# GPS_CAM-M8Q.net
KiCad netlist of a schematic drawn in Altium Designer
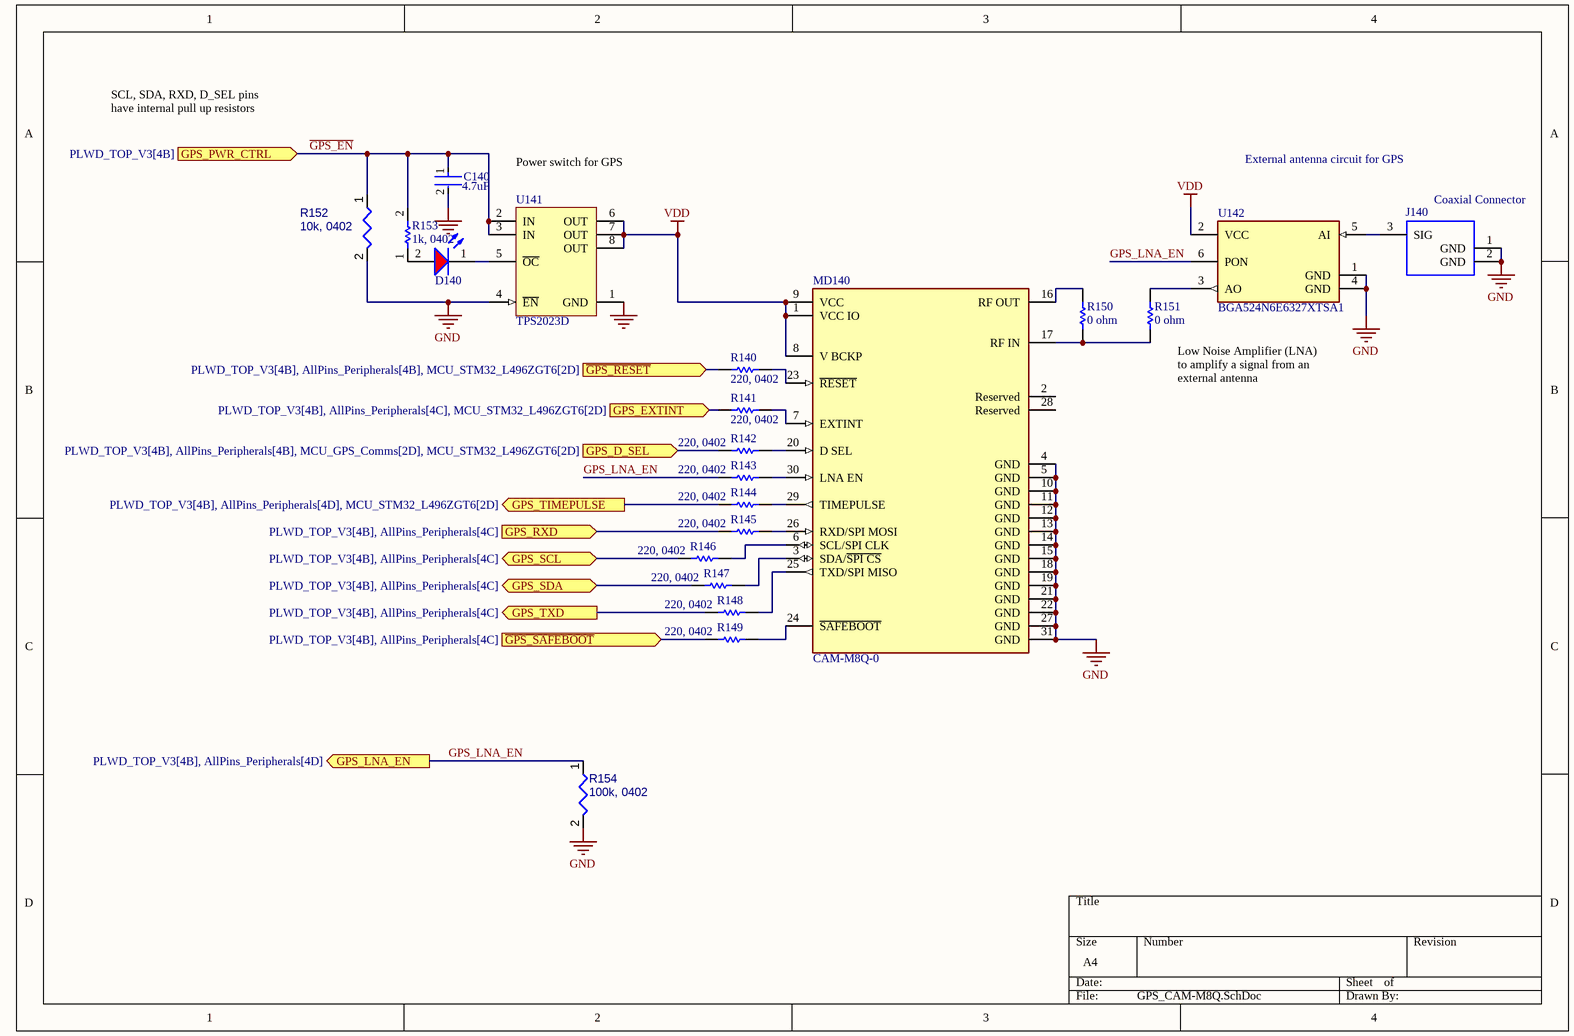
[diagram p0: GPS_CAM-M8Q.SchDoc]

(export (version "E")
  (design (tool "Eeschema 10.0.6"))
  (components
    (comp (ref "C140")
      (value "CL05A475MP5NRNC")
      (footprint "FP-CL282-IPC_C")
      (description "Cap Ceramic 4.7uF 10V X5R ±20% SMD 0402 +85°C Paper T/R")
      (fields (field (name "CAPACITANCE") "4.7uF") (field (name "TOLERANCE") "20%"))
      (libsource (lib "Altium Content Vault") (part "b4654b650e69147ec39a6b967a45e02"))
    )
    (comp (ref "D140")
      (value "150120SS75000")
      (footprint "WL-SMCW_1206_150120xx75000")
      (libsource (lib "Altium Content Vault") (part "LED_Red_2A-1K"))
    )
    (comp (ref "J140")
      (value "Coaxial Connector")
      (footprint "HRS-U.FL-R-SMT_V")
      (fields (field (name "MANUFACTURER") "Hirose Electric"))
      (libsource (lib "Carleton University") (part "HRS-U.FL-R-SMT-3"))
    )
    (comp (ref "MD140")
      (value "CAM-M8Q-0")
      (footprint "FP-CAM-M8Q-0-MFG")
      (description "RF RCVR GNSS/GPS 1.575GHZ MODULE")
      (fields
        (field (name "OCTOPART") "https://octopart.com/cam-m8q-0-u-blox-54356730")
        (field (name "MANUFACTURER") "u-blox")
      )
      (libsource (lib "Altium Content Vault") (part "ce05b97091f8f71e8eae4fd8376787f"))
    )
    (comp (ref "R140")
      (value "220, 0402")
      (footprint "RESC1005X40X25LL10T10")
      (fields (field (name "PART NUMBER") "RK73H1ETTP2200F") (field (name "MANUFACTURER") "KOA Speer"))
      (libsource (lib "Altium Content Vault") (part "RES"))
    )
    (comp (ref "R141")
      (value "220, 0402")
      (footprint "RESC1005X40X25LL10T10")
      (fields (field (name "PART NUMBER") "RK73H1ETTP2200F") (field (name "MANUFACTURER") "KOA Speer"))
      (libsource (lib "Altium Content Vault") (part "RES"))
    )
    (comp (ref "R142")
      (value "220, 0402")
      (footprint "RESC1005X40X25LL10T10")
      (fields (field (name "PART NUMBER") "RK73H1ETTP2200F") (field (name "MANUFACTURER") "KOA Speer"))
      (libsource (lib "Altium Content Vault") (part "RES"))
    )
    (comp (ref "R143")
      (value "220, 0402")
      (footprint "RESC1005X40X25LL10T10")
      (fields (field (name "PART NUMBER") "RK73H1ETTP2200F") (field (name "MANUFACTURER") "KOA Speer"))
      (libsource (lib "Altium Content Vault") (part "RES"))
    )
    (comp (ref "R144")
      (value "220, 0402")
      (footprint "RESC1005X40X25LL10T10")
      (fields (field (name "PART NUMBER") "RK73H1ETTP2200F") (field (name "MANUFACTURER") "KOA Speer"))
      (libsource (lib "Altium Content Vault") (part "RES"))
    )
    (comp (ref "R145")
      (value "220, 0402")
      (footprint "RESC1005X40X25LL10T10")
      (fields (field (name "PART NUMBER") "RK73H1ETTP2200F") (field (name "MANUFACTURER") "KOA Speer"))
      (libsource (lib "Altium Content Vault") (part "RES"))
    )
    (comp (ref "R146")
      (value "220, 0402")
      (footprint "RESC1005X40X25LL10T10")
      (fields (field (name "PART NUMBER") "RK73H1ETTP2200F") (field (name "MANUFACTURER") "KOA Speer"))
      (libsource (lib "Altium Content Vault") (part "RES"))
    )
    (comp (ref "R147")
      (value "220, 0402")
      (footprint "RESC1005X40X25LL10T10")
      (fields (field (name "PART NUMBER") "RK73H1ETTP2200F") (field (name "MANUFACTURER") "KOA Speer"))
      (libsource (lib "Altium Content Vault") (part "RES"))
    )
    (comp (ref "R148")
      (value "220, 0402")
      (footprint "RESC1005X40X25LL10T10")
      (fields (field (name "PART NUMBER") "RK73H1ETTP2200F") (field (name "MANUFACTURER") "KOA Speer"))
      (libsource (lib "Altium Content Vault") (part "RES"))
    )
    (comp (ref "R149")
      (value "220, 0402")
      (footprint "RESC1005X40X25LL10T10")
      (fields (field (name "PART NUMBER") "RK73H1ETTP2200F") (field (name "MANUFACTURER") "KOA Speer"))
      (libsource (lib "Altium Content Vault") (part "RES"))
    )
    (comp (ref "R150")
      (value "0 ohm")
      (footprint "RESC1005X40X25LL05T10")
      (fields (field (name "MANUFACTURER") "Panasonic") (field (name "PART NUMBER") "ERJ-S020R00X"))
      (libsource (lib "Altium Content Vault") (part "RES"))
    )
    (comp (ref "R151")
      (value "0 ohm")
      (footprint "RESC1005X40X25LL05T10")
      (fields (field (name "MANUFACTURER") "Panasonic") (field (name "PART NUMBER") "ERJ-S020R00X"))
      (libsource (lib "Altium Content Vault") (part "RES"))
    )
    (comp (ref "R152")
      (value "10k, 0402")
      (footprint "RESC1005X40X25ML05T05")
      (description "Chip Resistor, 10 KOhm, +/- 1%, 0.1 W, -55 to 155 degC, 0402 (1005 Metric)")
      (fields (field (name "TOLERANCE") "1%") (field (name "POWER") "100mW"))
      (libsource (lib "") (part "RES-2_1"))
    )
    (comp (ref "R153")
      (value "1k, 0402")
      (footprint "RESC1005X40X25ML05T05")
      (description "Chip Resistor, 1 KOhm, +/- 1%, 0.1 W, -55 to 155 degC, 0402 (1005 Metric)")
      (fields (field (name "POWER") "100mW") (field (name "TOLERANCE") "1%"))
      (libsource (lib "Carleton University") (part "RES-2"))
    )
    (comp (ref "R154")
      (value "100k, 0402")
      (footprint "RESC1005X40X25ML05T05")
      (description "Chip Resistor, 100 KOhm, +/- 1%, 0.1 W, -55 to 155 degC, 0402 (1005 Metric)")
      (fields (field (name "POWER") "100mW") (field (name "TOLERANCE") "1%"))
      (libsource (lib "") (part "RES-2_1"))
    )
    (comp (ref "U141")
      (value "TPS2023D")
      (footprint "D0008A_M")
      (fields (field (name "MANUFACTURER") "Texas Instruments"))
      (libsource (lib "Altium Content Vault") (part "TI-TPS2023D8"))
    )
    (comp (ref "U142")
      (value "BGA524N6E6327XTSA1")
      (footprint "FP-PG-TSNP-6-MFG")
      (description "IC AMP GPS 1.55-1.615GHZ TSNP6-2")
      (libsource (lib "Altium Content Vault") (part "f76d869b63f6dd4e076b8b444429d3f"))
    )
  )
  (nets
    (net (code "1") (name "/GPS_D_SEL") (class "Default")
      (node (ref "R142") (pin "2") (pinfunction "2_2") (pintype "passive"))
    )
    (net (code "2") (name "/GPS_EXTINT") (class "Default")
      (node (ref "R141") (pin "2") (pinfunction "2_2") (pintype "passive"))
    )
    (net (code "3") (name "/GPS_LNA_EN") (class "Default")
      (node (ref "R143") (pin "2") (pinfunction "2_2") (pintype "passive"))
      (node (ref "R154") (pin "1") (pinfunction "1_1") (pintype "passive"))
      (node (ref "U142") (pin "6") (pinfunction "PON_6") (pintype "power_in"))
    )
    (net (code "4") (name "/GPS_RXD") (class "Default")
      (node (ref "R145") (pin "2") (pinfunction "2_2") (pintype "passive"))
    )
    (net (code "5") (name "/GPS_SCL") (class "Default")
      (node (ref "R146") (pin "2") (pinfunction "2_2") (pintype "passive"))
    )
    (net (code "6") (name "/GPS_SDA") (class "Default")
      (node (ref "R147") (pin "2") (pinfunction "2_2") (pintype "passive"))
    )
    (net (code "7") (name "/GPS_TIMEPULSE") (class "Default")
      (node (ref "R144") (pin "2") (pinfunction "2_2") (pintype "passive"))
    )
    (net (code "8") (name "/GPS_TXD") (class "Default")
      (node (ref "R148") (pin "2") (pinfunction "2_2") (pintype "passive"))
    )
    (net (code "9") (name "/~{GPS_EN}") (class "Default")
      (node (ref "C140") (pin "1") (pinfunction "1_1") (pintype "passive"))
      (node (ref "R152") (pin "1") (pinfunction "1_1") (pintype "passive"))
      (node (ref "R153") (pin "2") (pinfunction "2_2") (pintype "passive"))
      (node (ref "U141") (pin "2") (pinfunction "IN_2") (pintype "power_in"))
      (node (ref "U141") (pin "3") (pinfunction "IN_3") (pintype "power_in"))
    )
    (net (code "10") (name "/~{GPS_RESET}") (class "Default")
      (node (ref "R140") (pin "2") (pinfunction "2_2") (pintype "passive"))
    )
    (net (code "11") (name "/~{GPS_SAFEBOOT}") (class "Default")
      (node (ref "R149") (pin "2") (pinfunction "2_2") (pintype "passive"))
    )
    (net (code "12") (name "GND") (class "Default")
      (node (ref "C140") (pin "2") (pinfunction "2_2") (pintype "passive"))
      (node (ref "J140") (pin "1") (pinfunction "GND_1") (pintype "power_in"))
      (node (ref "J140") (pin "2") (pinfunction "GND_2") (pintype "power_in"))
      (node (ref "MD140") (pin "10") (pinfunction "GND_10") (pintype "power_in"))
      (node (ref "MD140") (pin "11") (pinfunction "GND_11") (pintype "power_in"))
      (node (ref "MD140") (pin "12") (pinfunction "GND_12") (pintype "power_in"))
      (node (ref "MD140") (pin "13") (pinfunction "GND_13") (pintype "power_in"))
      (node (ref "MD140") (pin "14") (pinfunction "GND_14") (pintype "power_in"))
      (node (ref "MD140") (pin "15") (pinfunction "GND_15") (pintype "power_in"))
      (node (ref "MD140") (pin "18") (pinfunction "GND_18") (pintype "power_in"))
      (node (ref "MD140") (pin "19") (pinfunction "GND_19") (pintype "power_in"))
      (node (ref "MD140") (pin "21") (pinfunction "GND_21") (pintype "power_in"))
      (node (ref "MD140") (pin "22") (pinfunction "GND_22") (pintype "power_in"))
      (node (ref "MD140") (pin "27") (pinfunction "GND_27") (pintype "power_in"))
      (node (ref "MD140") (pin "31") (pinfunction "GND_31") (pintype "power_in"))
      (node (ref "MD140") (pin "4") (pinfunction "GND_4") (pintype "power_in"))
      (node (ref "MD140") (pin "5") (pinfunction "GND_5") (pintype "power_in"))
      (node (ref "R152") (pin "2") (pinfunction "2_2") (pintype "passive"))
      (node (ref "R154") (pin "2") (pinfunction "2_2") (pintype "passive"))
      (node (ref "U141") (pin "1") (pinfunction "GND_1") (pintype "power_in"))
      (node (ref "U141") (pin "4") (pinfunction "~{EN}_4") (pintype "input"))
      (node (ref "U142") (pin "1") (pinfunction "GND_1") (pintype "power_in"))
      (node (ref "U142") (pin "4") (pinfunction "GND_4") (pintype "power_in"))
    )
    (net (code "13") (name "Net-(D140-A)") (class "Default")
      (node (ref "D140") (pin "2") (pinfunction "A_2") (pintype "passive"))
      (node (ref "R153") (pin "1") (pinfunction "1_1") (pintype "passive"))
    )
    (net (code "14") (name "Net-(D140-K)") (class "Default")
      (node (ref "D140") (pin "1") (pinfunction "K_1") (pintype "passive"))
      (node (ref "U141") (pin "5") (pinfunction "~{OC}_5") (pintype "open_collector"))
    )
    (net (code "15") (name "Net-(J140-SIG)") (class "Default")
      (node (ref "J140") (pin "3") (pinfunction "SIG_3") (pintype "passive"))
      (node (ref "U142") (pin "5") (pinfunction "AI_5") (pintype "input"))
    )
    (net (code "16") (name "Net-(MD140-D_SEL)") (class "Default")
      (node (ref "MD140") (pin "20") (pinfunction "D_SEL_20") (pintype "input"))
      (node (ref "R142") (pin "1") (pinfunction "1_1") (pintype "passive"))
    )
    (net (code "17") (name "Net-(MD140-EXTINT)") (class "Default")
      (node (ref "MD140") (pin "7") (pinfunction "EXTINT_7") (pintype "input"))
      (node (ref "R141") (pin "1") (pinfunction "1_1") (pintype "passive"))
    )
    (net (code "18") (name "Net-(MD140-LNA_EN)") (class "Default")
      (node (ref "MD140") (pin "30") (pinfunction "LNA_EN_30") (pintype "input"))
      (node (ref "R143") (pin "1") (pinfunction "1_1") (pintype "passive"))
    )
    (net (code "19") (name "Net-(MD140-RF_IN)") (class "Default")
      (node (ref "MD140") (pin "17") (pinfunction "RF_IN_17") (pintype "tri_state"))
      (node (ref "R150") (pin "1") (pinfunction "1_1") (pintype "passive"))
      (node (ref "R151") (pin "1") (pinfunction "1_1") (pintype "passive"))
    )
    (net (code "20") (name "Net-(MD140-RF_OUT)") (class "Default")
      (node (ref "MD140") (pin "16") (pinfunction "RF_OUT_16") (pintype "passive"))
      (node (ref "R150") (pin "2") (pinfunction "2_2") (pintype "passive"))
    )
    (net (code "21") (name "Net-(MD140-RXD{slash}SPI_MOSI)") (class "Default")
      (node (ref "MD140") (pin "26") (pinfunction "RXD/SPI_MOSI_26") (pintype "input"))
      (node (ref "R145") (pin "1") (pinfunction "1_1") (pintype "passive"))
    )
    (net (code "22") (name "Net-(MD140-SCL{slash}SPI_CLK)") (class "Default")
      (node (ref "MD140") (pin "6") (pinfunction "SCL/SPI_CLK_6") (pintype "bidirectional"))
      (node (ref "R146") (pin "1") (pinfunction "1_1") (pintype "passive"))
    )
    (net (code "23") (name "Net-(MD140-SDA{slash}~{SPI_CS})") (class "Default")
      (node (ref "MD140") (pin "3") (pinfunction "SDA/~{SPI_CS}_3") (pintype "bidirectional"))
      (node (ref "R147") (pin "1") (pinfunction "1_1") (pintype "passive"))
    )
    (net (code "24") (name "Net-(MD140-TIMEPULSE)") (class "Default")
      (node (ref "MD140") (pin "29") (pinfunction "TIMEPULSE_29") (pintype "output"))
      (node (ref "R144") (pin "1") (pinfunction "1_1") (pintype "passive"))
    )
    (net (code "25") (name "Net-(MD140-TXD{slash}SPI_MISO)") (class "Default")
      (node (ref "MD140") (pin "25") (pinfunction "TXD/SPI_MISO_25") (pintype "output"))
      (node (ref "R148") (pin "1") (pinfunction "1_1") (pintype "passive"))
    )
    (net (code "26") (name "Net-(MD140-~{RESET})") (class "Default")
      (node (ref "MD140") (pin "23") (pinfunction "~{RESET}_23") (pintype "input"))
      (node (ref "R140") (pin "1") (pinfunction "1_1") (pintype "passive"))
    )
    (net (code "27") (name "Net-(MD140-~{SAFEBOOT})") (class "Default")
      (node (ref "MD140") (pin "24") (pinfunction "~{SAFEBOOT}_24") (pintype "passive"))
      (node (ref "R149") (pin "1") (pinfunction "1_1") (pintype "passive"))
    )
    (net (code "28") (name "Net-(U142-AO)") (class "Default")
      (node (ref "R151") (pin "2") (pinfunction "2_2") (pintype "passive"))
      (node (ref "U142") (pin "3") (pinfunction "AO_3") (pintype "output"))
    )
    (net (code "29") (name "VDD") (class "Default")
      (node (ref "MD140") (pin "1") (pinfunction "VCC_IO_1") (pintype "power_in"))
      (node (ref "MD140") (pin "8") (pinfunction "V_BCKP_8") (pintype "power_in"))
      (node (ref "MD140") (pin "9") (pinfunction "VCC_9") (pintype "power_in"))
      (node (ref "U141") (pin "6") (pinfunction "OUT_6") (pintype "power_in"))
      (node (ref "U141") (pin "7") (pinfunction "OUT_7") (pintype "power_in"))
      (node (ref "U141") (pin "8") (pinfunction "OUT_8") (pintype "power_in"))
      (node (ref "U142") (pin "2") (pinfunction "VCC_2") (pintype "power_in"))
    )
    (net (code "30") (name "unconnected-(MD140-Reserved-Pad2)") (class "Default")
      (node (ref "MD140") (pin "2") (pinfunction "Reserved_2") (pintype "passive"))
    )
    (net (code "31") (name "unconnected-(MD140-Reserved-Pad28)") (class "Default")
      (node (ref "MD140") (pin "28") (pinfunction "Reserved_28") (pintype "passive"))
    )
  )
)
